# sync-demod-ic.net
KiCad netlist of a schematic drawn in Altium Designer
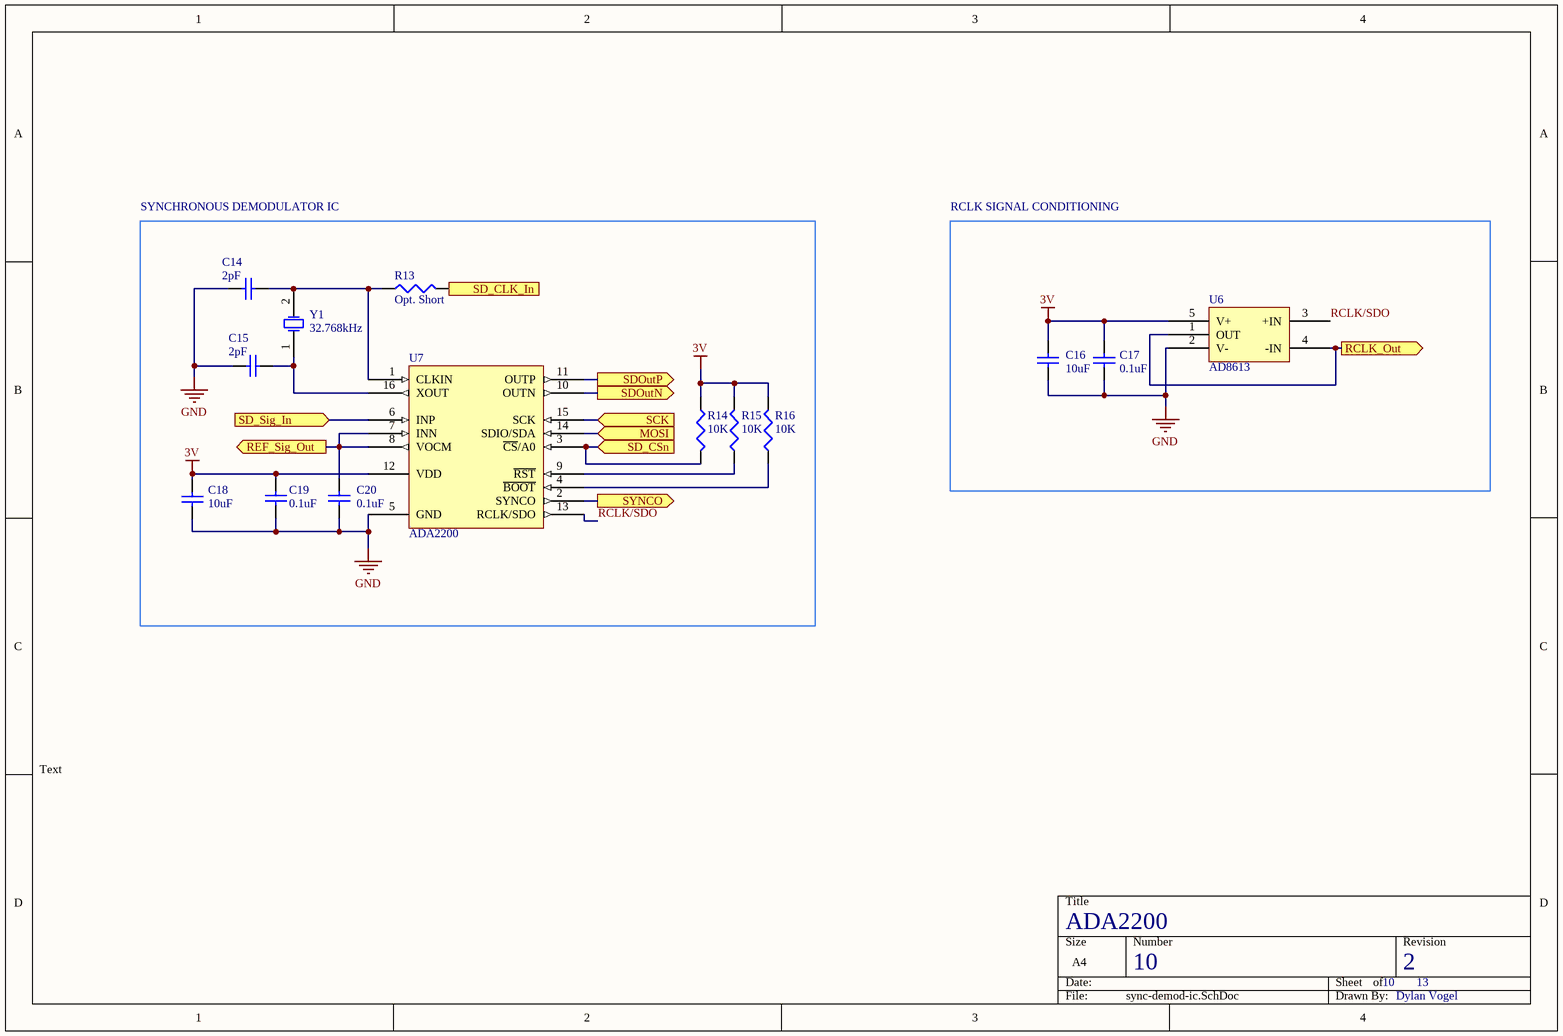
[diagram p0: sync-demod-ic.SchDoc]

(export (version "E")
  (design (tool "Eeschema 10.0.6"))
  (components
    (comp (ref "C14")
      (value "2pF")
      (footprint "0402")
      (description "Capacitor (Semiconductor SIM Model)")
      (fields (field (name "PUBLISHER") "Altium Limited"))
      (libsource (lib "Miscellaneous Devices") (part "Cap Semi"))
    )
    (comp (ref "C15")
      (value "2pF")
      (footprint "0402")
      (description "Capacitor (Semiconductor SIM Model)")
      (fields (field (name "PUBLISHER") "Altium Limited"))
      (libsource (lib "Miscellaneous Devices") (part "Cap Semi"))
    )
    (comp (ref "C16")
      (value "10uF")
      (footprint "1608[0603]")
      (description "Capacitor (Semiconductor SIM Model)")
      (fields (field (name "PUBLISHER") "Altium Limited"))
      (libsource (lib "Miscellaneous Devices") (part "Cap Semi"))
    )
    (comp (ref "C17")
      (value "0.1uF")
      (footprint "0402")
      (description "Capacitor (Semiconductor SIM Model)")
      (fields (field (name "PUBLISHER") "Altium Limited"))
      (libsource (lib "Miscellaneous Devices") (part "Cap Semi"))
    )
    (comp (ref "C18")
      (value "10uF")
      (footprint "1608[0603]")
      (description "Capacitor (Semiconductor SIM Model)")
      (fields (field (name "PUBLISHER") "Altium Limited"))
      (libsource (lib "Miscellaneous Devices") (part "Cap Semi"))
    )
    (comp (ref "C19")
      (value "0.1uF")
      (footprint "0402")
      (description "Capacitor (Semiconductor SIM Model)")
      (fields (field (name "PUBLISHER") "Altium Limited"))
      (libsource (lib "Miscellaneous Devices") (part "Cap Semi"))
    )
    (comp (ref "C20")
      (value "0.1uF")
      (footprint "0402")
      (description "Capacitor (Semiconductor SIM Model)")
      (fields (field (name "PUBLISHER") "Altium Limited"))
      (libsource (lib "Miscellaneous Devices") (part "Cap Semi"))
    )
    (comp (ref "R13")
      (value "Opt. Short")
      (footprint "0402")
      (description "Optional short to connect 32M1 rather than Y1")
      (fields (field (name "PUBLISHER") "Altium Limited"))
      (libsource (lib "Miscellaneous Devices") (part "Res3"))
    )
    (comp (ref "R14")
      (value "10K")
      (footprint "0402")
      (description "Resistor")
      (fields (field (name "PUBLISHER") "Altium Limited"))
      (libsource (lib "Miscellaneous Devices") (part "Res3"))
    )
    (comp (ref "R15")
      (value "10K")
      (footprint "0402")
      (description "Resistor")
      (fields (field (name "PUBLISHER") "Altium Limited"))
      (libsource (lib "Miscellaneous Devices") (part "Res3"))
    )
    (comp (ref "R16")
      (value "10K")
      (footprint "0402")
      (description "Resistor")
      (fields (field (name "PUBLISHER") "Altium Limited"))
      (libsource (lib "Miscellaneous Devices") (part "Res3"))
    )
    (comp (ref "U6")
      (value "AD8613")
      (footprint "SOP-65P200X125-5N")
      (description "Low power, low noise rail-to-rail op-amp.")
      (libsource (lib "PAY") (part "AD8613"))
    )
    (comp (ref "U7")
      (value "ADA2200")
      (footprint "SSOP16_N")
      (description "Synchronous demodulator and configurable analog filter.")
      (libsource (lib "PAY") (part "ADA2200"))
    )
    (comp (ref "Y1")
      (value "32.768kHz")
      (footprint "ABS07-120-32.768")
      (description "Crystal Oscillator")
      (fields (field (name "PUBLISHER") "Altium Limited"))
      (libsource (lib "Miscellaneous Devices") (part "XTAL"))
    )
  )
  (nets
    (net (code "1") (name "/MOSI") (class "Default")
      (node (ref "U7") (pin "14") (pinfunction "SDIO/SDA_14") (pintype "input"))
    )
    (net (code "2") (name "/RCLK_Out") (class "Default")
      (node (ref "U6") (pin "1") (pinfunction "OUT_1") (pintype "passive"))
      (node (ref "U6") (pin "4") (pinfunction "-IN_4") (pintype "passive"))
    )
    (net (code "3") (name "/RCLK{slash}SDO") (class "Default")
      (node (ref "U6") (pin "3") (pinfunction "+IN_3") (pintype "passive"))
      (node (ref "U7") (pin "13") (pinfunction "RCLK/SDO_13") (pintype "output"))
    )
    (net (code "4") (name "/REF_Sig_Out") (class "Default")
      (node (ref "C20") (pin "2") (pinfunction "2_2") (pintype "passive"))
      (node (ref "U7") (pin "7") (pinfunction "INN_7") (pintype "input"))
      (node (ref "U7") (pin "8") (pinfunction "VOCM_8") (pintype "output"))
    )
    (net (code "5") (name "/SCK") (class "Default")
      (node (ref "U7") (pin "15") (pinfunction "SCK_15") (pintype "input"))
    )
    (net (code "6") (name "/SDOutN") (class "Default")
      (node (ref "U7") (pin "10") (pinfunction "OUTN_10") (pintype "output"))
    )
    (net (code "7") (name "/SDOutP") (class "Default")
      (node (ref "U7") (pin "11") (pinfunction "OUTP_11") (pintype "output"))
    )
    (net (code "8") (name "/SD_CLK_In") (class "Default")
      (node (ref "R13") (pin "2") (pinfunction "2_2") (pintype "passive"))
    )
    (net (code "9") (name "/SD_CSn") (class "Default")
      (node (ref "R14") (pin "2") (pinfunction "2_2") (pintype "passive"))
      (node (ref "U7") (pin "3") (pinfunction "~{CS}/A0_3") (pintype "input"))
    )
    (net (code "10") (name "/SD_Sig_In") (class "Default")
      (node (ref "U7") (pin "6") (pinfunction "INP_6") (pintype "input"))
    )
    (net (code "11") (name "/SYNCO") (class "Default")
      (node (ref "U7") (pin "2") (pinfunction "SYNCO_2") (pintype "output"))
    )
    (net (code "12") (name "3V") (class "Default")
      (node (ref "C16") (pin "2") (pinfunction "2_2") (pintype "passive"))
      (node (ref "C17") (pin "2") (pinfunction "2_2") (pintype "passive"))
      (node (ref "C18") (pin "1") (pinfunction "1_1") (pintype "passive"))
      (node (ref "C19") (pin "2") (pinfunction "2_2") (pintype "passive"))
      (node (ref "R14") (pin "1") (pinfunction "1_1") (pintype "passive"))
      (node (ref "R15") (pin "2") (pinfunction "2_2") (pintype "passive"))
      (node (ref "R16") (pin "2") (pinfunction "2_2") (pintype "passive"))
      (node (ref "U6") (pin "5") (pinfunction "V+_5") (pintype "passive"))
      (node (ref "U7") (pin "12") (pinfunction "VDD_12") (pintype "power_in"))
    )
    (net (code "13") (name "GND") (class "Default")
      (node (ref "C14") (pin "2") (pinfunction "2_2") (pintype "passive"))
      (node (ref "C15") (pin "2") (pinfunction "2_2") (pintype "passive"))
      (node (ref "C16") (pin "1") (pinfunction "1_1") (pintype "passive"))
      (node (ref "C17") (pin "1") (pinfunction "1_1") (pintype "passive"))
      (node (ref "C18") (pin "2") (pinfunction "2_2") (pintype "passive"))
      (node (ref "C19") (pin "1") (pinfunction "1_1") (pintype "passive"))
      (node (ref "C20") (pin "1") (pinfunction "1_1") (pintype "passive"))
      (node (ref "U6") (pin "2") (pinfunction "V-_2") (pintype "passive"))
      (node (ref "U7") (pin "5") (pinfunction "GND_5") (pintype "power_in"))
    )
    (net (code "14") (name "Net-(U7-CLKIN)") (class "Default")
      (node (ref "C14") (pin "1") (pinfunction "1_1") (pintype "passive"))
      (node (ref "R13") (pin "1") (pinfunction "1_1") (pintype "passive"))
      (node (ref "U7") (pin "1") (pinfunction "CLKIN_1") (pintype "input"))
      (node (ref "Y1") (pin "2") (pinfunction "OSC2_2") (pintype "passive"))
    )
    (net (code "15") (name "Net-(U7-XOUT)") (class "Default")
      (node (ref "C15") (pin "1") (pinfunction "1_1") (pintype "passive"))
      (node (ref "U7") (pin "16") (pinfunction "XOUT_16") (pintype "output"))
      (node (ref "Y1") (pin "1") (pinfunction "OSC1_1") (pintype "passive"))
    )
    (net (code "16") (name "Net-(U7-~{BOOT})") (class "Default")
      (node (ref "R16") (pin "1") (pinfunction "1_1") (pintype "passive"))
      (node (ref "U7") (pin "4") (pinfunction "~{BOOT}_4") (pintype "input"))
    )
    (net (code "17") (name "Net-(U7-~{RST})") (class "Default")
      (node (ref "R15") (pin "1") (pinfunction "1_1") (pintype "passive"))
      (node (ref "U7") (pin "9") (pinfunction "~{RST}_9") (pintype "input"))
    )
  )
)
